# ring_counter.net
KiCad netlist of a schematic drawn in EAGLE
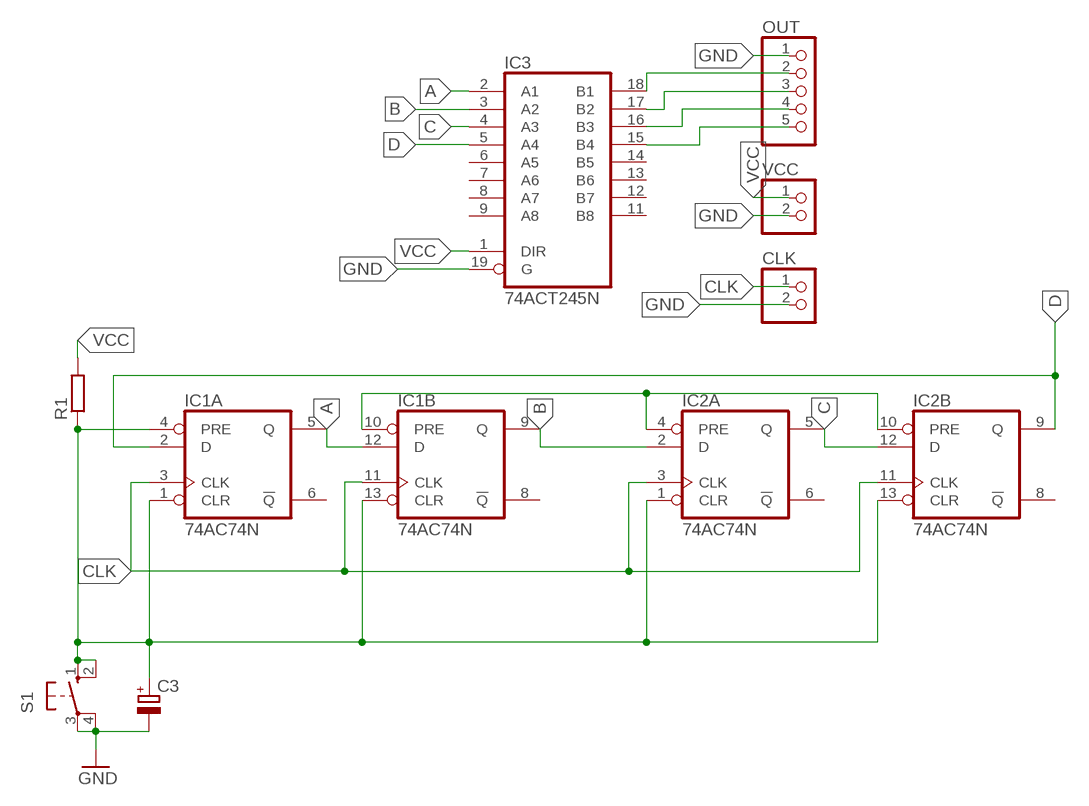
[diagram p0: schematic, sheet 1]

(export (version "E")
  (design (tool "Eeschema 10.0.6"))
  (components
    (comp (ref "C3")
      (value "CPOL-EUE2,5-6E")
      (footprint "eagle-import:E2,5-6E")
      (libsource (lib "eagle-import") (part "CPOL-EUE2,5-6E"))
    )
    (comp (ref "CLK")
      (value "PINHD-1X2")
      (footprint "eagle-import:1X02")
      (libsource (lib "eagle-import") (part "PINHD-1X2"))
    )
    (comp (ref "IC1")
      (value "74AC74N")
      (footprint "eagle-import:DIL14")
      (libsource (lib "eagle-import") (part "7474NAC"))
    )
    (comp (ref "IC2")
      (value "74AC74N")
      (footprint "eagle-import:DIL14")
      (libsource (lib "eagle-import") (part "7474NAC"))
    )
    (comp (ref "IC3")
      (value "74ACT245N")
      (footprint "eagle-import:DIL20")
      (libsource (lib "eagle-import") (part "74245NACT"))
    )
    (comp (ref "OUT")
      (value "PINHD-1X5")
      (footprint "eagle-import:1X05")
      (libsource (lib "eagle-import") (part "PINHD-1X5"))
    )
    (comp (ref "R1")
      (value "R-EU_0207/12")
      (footprint "eagle-import:0207_12")
      (libsource (lib "eagle-import") (part "R-EU_0207/12"))
    )
    (comp (ref "S1")
      (value "10-XX")
      (footprint "eagle-import:B3F-10XX")
      (fields (field (name "MPN") "B3F-1000"))
      (libsource (lib "eagle-import") (part "10-XX"))
    )
    (comp (ref "VCC")
      (value "PINHD-1X2")
      (footprint "eagle-import:1X02")
      (libsource (lib "eagle-import") (part "PINHD-1X2"))
    )
  )
  (nets
    (net (code "1") (name "A") (class "Default")
      (node (ref "IC1") (pin "12") (pinfunction "D_12") (pintype "input"))
      (node (ref "IC1") (pin "5") (pinfunction "Q_5") (pintype "output"))
      (node (ref "IC3") (pin "2") (pinfunction "A1_2") (pintype "bidirectional"))
    )
    (net (code "2") (name "B") (class "Default")
      (node (ref "IC1") (pin "9") (pinfunction "Q_9") (pintype "output"))
      (node (ref "IC2") (pin "2") (pinfunction "D_2") (pintype "input"))
      (node (ref "IC3") (pin "3") (pinfunction "A2_3") (pintype "bidirectional"))
    )
    (net (code "3") (name "C") (class "Default")
      (node (ref "IC2") (pin "12") (pinfunction "D_12") (pintype "input"))
      (node (ref "IC2") (pin "5") (pinfunction "Q_5") (pintype "output"))
      (node (ref "IC3") (pin "4") (pinfunction "A3_4") (pintype "bidirectional"))
    )
    (net (code "4") (name "CLK") (class "Default")
      (node (ref "CLK") (pin "1") (pinfunction "1_1") (pintype "passive"))
      (node (ref "IC1") (pin "11") (pinfunction "CLK_11") (pintype "input"))
      (node (ref "IC1") (pin "3") (pinfunction "CLK_3") (pintype "input"))
      (node (ref "IC2") (pin "11") (pinfunction "CLK_11") (pintype "input"))
      (node (ref "IC2") (pin "3") (pinfunction "CLK_3") (pintype "input"))
    )
    (net (code "5") (name "D") (class "Default")
      (node (ref "IC1") (pin "2") (pinfunction "D_2") (pintype "input"))
      (node (ref "IC2") (pin "9") (pinfunction "Q_9") (pintype "output"))
      (node (ref "IC3") (pin "5") (pinfunction "A4_5") (pintype "bidirectional"))
    )
    (net (code "6") (name "GND") (class "Default")
      (node (ref "C3") (pin "-") (pinfunction "-_-") (pintype "passive"))
      (node (ref "CLK") (pin "2") (pinfunction "2_2") (pintype "passive"))
      (node (ref "IC3") (pin "19") (pinfunction "G_19") (pintype "input"))
      (node (ref "OUT") (pin "1") (pinfunction "1_1") (pintype "passive"))
      (node (ref "S1") (pin "3") (pinfunction "P_3") (pintype "passive"))
      (node (ref "S1") (pin "4") (pinfunction "P1_4") (pintype "passive"))
      (node (ref "VCC") (pin "2") (pinfunction "2_2") (pintype "passive"))
    )
    (net (code "7") (name "Net-(IC1A-CLR)") (class "Default")
      (node (ref "C3") (pin "+") (pinfunction "+_+") (pintype "passive"))
      (node (ref "IC1") (pin "1") (pinfunction "CLR_1") (pintype "input"))
      (node (ref "IC1") (pin "13") (pinfunction "CLR_13") (pintype "input"))
      (node (ref "IC1") (pin "4") (pinfunction "PRE_4") (pintype "input"))
      (node (ref "IC2") (pin "1") (pinfunction "CLR_1") (pintype "input"))
      (node (ref "IC2") (pin "13") (pinfunction "CLR_13") (pintype "input"))
      (node (ref "R1") (pin "1") (pinfunction "1_1") (pintype "passive"))
      (node (ref "S1") (pin "1") (pinfunction "S_1") (pintype "passive"))
      (node (ref "S1") (pin "2") (pinfunction "S1_2") (pintype "passive"))
    )
    (net (code "8") (name "Net-(IC1B-PRE)") (class "Default")
      (node (ref "IC1") (pin "10") (pinfunction "PRE_10") (pintype "input"))
      (node (ref "IC2") (pin "10") (pinfunction "PRE_10") (pintype "input"))
      (node (ref "IC2") (pin "4") (pinfunction "PRE_4") (pintype "input"))
    )
    (net (code "9") (name "Net-(IC3A-B1)") (class "Default")
      (node (ref "IC3") (pin "18") (pinfunction "B1_18") (pintype "bidirectional"))
      (node (ref "OUT") (pin "2") (pinfunction "2_2") (pintype "passive"))
    )
    (net (code "10") (name "Net-(IC3A-B2)") (class "Default")
      (node (ref "IC3") (pin "17") (pinfunction "B2_17") (pintype "bidirectional"))
      (node (ref "OUT") (pin "3") (pinfunction "3_3") (pintype "passive"))
    )
    (net (code "11") (name "Net-(IC3A-B3)") (class "Default")
      (node (ref "IC3") (pin "16") (pinfunction "B3_16") (pintype "bidirectional"))
      (node (ref "OUT") (pin "4") (pinfunction "4_4") (pintype "passive"))
    )
    (net (code "12") (name "Net-(IC3A-B4)") (class "Default")
      (node (ref "IC3") (pin "15") (pinfunction "B4_15") (pintype "bidirectional"))
      (node (ref "OUT") (pin "5") (pinfunction "5_5") (pintype "passive"))
    )
    (net (code "13") (name "VCC") (class "Default")
      (node (ref "IC3") (pin "1") (pinfunction "DIR_1") (pintype "input"))
      (node (ref "R1") (pin "2") (pinfunction "2_2") (pintype "passive"))
      (node (ref "VCC") (pin "1") (pinfunction "1_1") (pintype "passive"))
    )
    (net (code "14") (name "unconnected-(IC1A-~{Q}-Pad6)") (class "Default")
      (node (ref "IC1") (pin "6") (pinfunction "~{Q}_6") (pintype "output"))
    )
    (net (code "15") (name "unconnected-(IC1B-~{Q}-Pad8)") (class "Default")
      (node (ref "IC1") (pin "8") (pinfunction "~{Q}_8") (pintype "output"))
    )
    (net (code "16") (name "unconnected-(IC2A-~{Q}-Pad6)") (class "Default")
      (node (ref "IC2") (pin "6") (pinfunction "~{Q}_6") (pintype "output"))
    )
    (net (code "17") (name "unconnected-(IC2B-~{Q}-Pad8)") (class "Default")
      (node (ref "IC2") (pin "8") (pinfunction "~{Q}_8") (pintype "output"))
    )
    (net (code "18") (name "unconnected-(IC3A-A5-Pad6)") (class "Default")
      (node (ref "IC3") (pin "6") (pinfunction "A5_6") (pintype "bidirectional"))
    )
    (net (code "19") (name "unconnected-(IC3A-A6-Pad7)") (class "Default")
      (node (ref "IC3") (pin "7") (pinfunction "A6_7") (pintype "bidirectional"))
    )
    (net (code "20") (name "unconnected-(IC3A-A7-Pad8)") (class "Default")
      (node (ref "IC3") (pin "8") (pinfunction "A7_8") (pintype "bidirectional"))
    )
    (net (code "21") (name "unconnected-(IC3A-A8-Pad9)") (class "Default")
      (node (ref "IC3") (pin "9") (pinfunction "A8_9") (pintype "bidirectional"))
    )
    (net (code "22") (name "unconnected-(IC3A-B5-Pad14)") (class "Default")
      (node (ref "IC3") (pin "14") (pinfunction "B5_14") (pintype "bidirectional"))
    )
    (net (code "23") (name "unconnected-(IC3A-B6-Pad13)") (class "Default")
      (node (ref "IC3") (pin "13") (pinfunction "B6_13") (pintype "bidirectional"))
    )
    (net (code "24") (name "unconnected-(IC3A-B7-Pad12)") (class "Default")
      (node (ref "IC3") (pin "12") (pinfunction "B7_12") (pintype "bidirectional"))
    )
    (net (code "25") (name "unconnected-(IC3A-B8-Pad11)") (class "Default")
      (node (ref "IC3") (pin "11") (pinfunction "B8_11") (pintype "bidirectional"))
    )
  )
)
